# Sheet1.net
KiCad netlist of a schematic drawn in Altium Designer
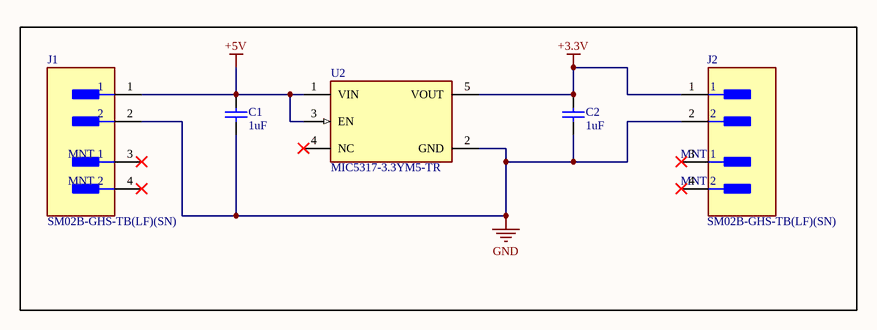
[diagram p0: Sheet1.SchDoc]

(export (version "E")
  (design (tool "Eeschema 10.0.6"))
  (components
    (comp (ref "C1")
      (value "1uF")
      (footprint "CAPC2013X145X50NL20T20")
      (fields (field (name "PART NUMBER") "VJ0805Y105KXQRW1BC") (field (name "MANUFACTURER") "Vitramon"))
      (libsource (lib "Altium Content Vault") (part "CAP"))
    )
    (comp (ref "C2")
      (value "1uF")
      (footprint "CAPC2013X145X50NL20T20")
      (fields (field (name "PART NUMBER") "VJ0805Y105KXQRW1BC") (field (name "MANUFACTURER") "Vitramon"))
      (libsource (lib "Altium Content Vault") (part "CAP"))
    )
    (comp (ref "J1")
      (value "SM02B-GHS-TB(LF)(SN)")
      (footprint "FP-SM02B-GHS-TB_LF_SN-MFG")
      (description "CONN HEADER SMD R/A 2POS 1.25MM")
      (libsource (lib "Altium Content Vault") (part "56ec3178a87b3978bdc1b3682cd516a"))
    )
    (comp (ref "J2")
      (value "SM02B-GHS-TB(LF)(SN)")
      (footprint "FP-SM02B-GHS-TB_LF_SN-MFG")
      (description "CONN HEADER SMD R/A 2POS 1.25MM")
      (libsource (lib "") (part "56ec3178a87b3978bdc1b3682cd516a_1"))
    )
    (comp (ref "U2")
      (value "MIC5317-3.3YM5-TR")
      (footprint "FP-SOT23-5LD-PL-1-MFG")
      (description "IC REG LINEAR 3.3V 150MA SOT23-5")
      (libsource (lib "Altium Content Vault") (part "0a093dae7315cdc977fd108dde87457"))
    )
  )
  (nets
    (net (code "1") (name "+3.3V") (class "Default")
      (node (ref "C2") (pin "1") (pinfunction "1_1") (pintype "passive"))
      (node (ref "J2") (pin "1") (pinfunction "1_1") (pintype "passive"))
      (node (ref "U2") (pin "5") (pinfunction "VOUT_5") (pintype "power_in"))
    )
    (net (code "2") (name "+5V") (class "Default")
      (node (ref "C1") (pin "1") (pinfunction "1_1") (pintype "passive"))
      (node (ref "J1") (pin "1") (pinfunction "1_1") (pintype "passive"))
      (node (ref "U2") (pin "1") (pinfunction "VIN_1") (pintype "power_in"))
      (node (ref "U2") (pin "3") (pinfunction "EN_3") (pintype "input"))
    )
    (net (code "3") (name "GND") (class "Default")
      (node (ref "C1") (pin "2") (pinfunction "2_2") (pintype "passive"))
      (node (ref "C2") (pin "2") (pinfunction "2_2") (pintype "passive"))
      (node (ref "J1") (pin "2") (pinfunction "2_2") (pintype "passive"))
      (node (ref "J2") (pin "2") (pinfunction "2_2") (pintype "passive"))
      (node (ref "U2") (pin "2") (pinfunction "GND_2") (pintype "power_in"))
    )
    (net (code "4") (name "unconnected-(J1-MNT_1-Pad3)") (class "Default")
      (node (ref "J1") (pin "3") (pinfunction "MNT_1_3") (pintype "passive+no_connect"))
    )
    (net (code "5") (name "unconnected-(J1-MNT_2-Pad4)") (class "Default")
      (node (ref "J1") (pin "4") (pinfunction "MNT_2_4") (pintype "passive+no_connect"))
    )
    (net (code "6") (name "unconnected-(J2-MNT_1-Pad3)") (class "Default")
      (node (ref "J2") (pin "3") (pinfunction "MNT_1_3") (pintype "passive+no_connect"))
    )
    (net (code "7") (name "unconnected-(J2-MNT_2-Pad4)") (class "Default")
      (node (ref "J2") (pin "4") (pinfunction "MNT_2_4") (pintype "passive+no_connect"))
    )
    (net (code "8") (name "unconnected-(U2-NC-Pad4)") (class "Default")
      (node (ref "U2") (pin "4") (pinfunction "NC_4") (pintype "passive+no_connect"))
    )
  )
)
